# MicroController.net
KiCad netlist of a schematic drawn in Altium Designer
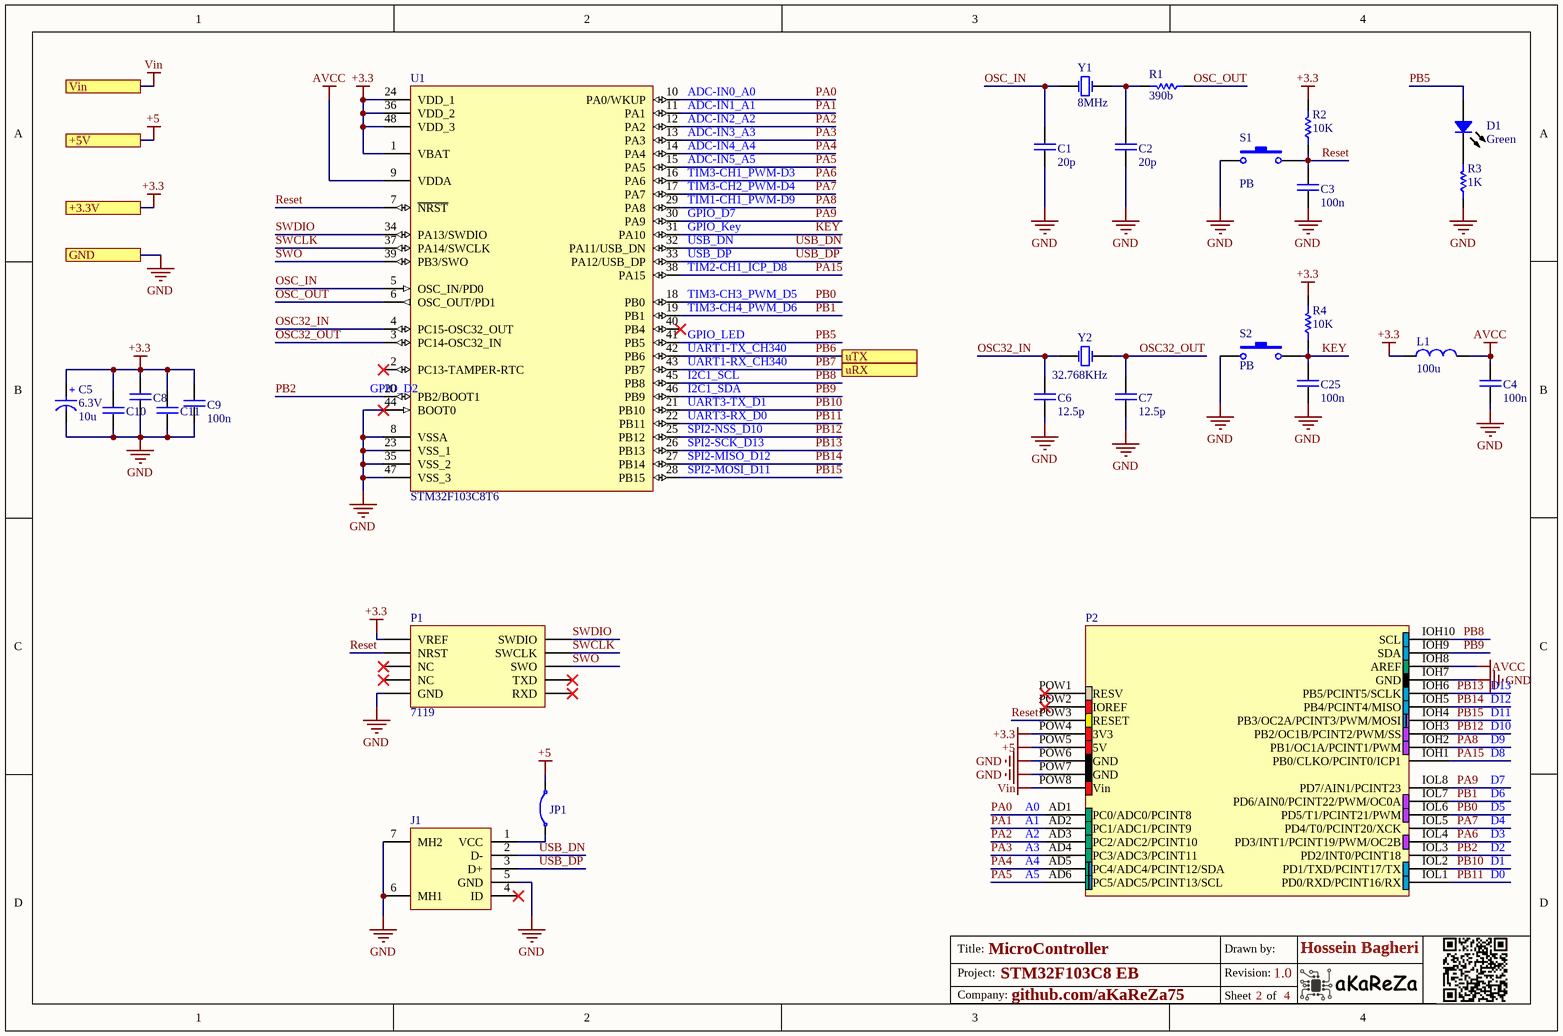
[diagram p0: MicroController.SchDoc]

(export (version "E")
  (design (tool "Eeschema 10.0.6"))
  (components
    (comp (ref "C1")
      (value "20p")
      (footprint "CAP 0603/1608")
      (description "Bipolar ceramic capacitor SMD")
      (fields (field (name "VALIDATION") "Valid"))
      (libsource (lib "aKaReZa") (part "Cap_Multi_SMD"))
    )
    (comp (ref "C2")
      (value "20p")
      (footprint "CAP 0603/1608")
      (description "Bipolar ceramic capacitor SMD")
      (fields (field (name "VALIDATION") "Valid"))
      (libsource (lib "aKaReZa") (part "Cap_Multi_SMD"))
    )
    (comp (ref "C3")
      (value "100n")
      (footprint "CAP 0805/2012")
      (description "Bipolar ceramic capacitor SMD")
      (fields (field (name "VALIDATION") "Valid"))
      (libsource (lib "aKaReZa") (part "Cap_Multi_SMD_100nF_0805"))
    )
    (comp (ref "C4")
      (value "100n")
      (footprint "CAP 0805/2012")
      (description "Bipolar ceramic capacitor SMD")
      (fields (field (name "VALIDATION") "Valid"))
      (libsource (lib "aKaReZa") (part "Cap_Multi_SMD_100nF_0805"))
    )
    (comp (ref "C5")
      (value "10u")
      (footprint "SMT_C_Tantalum_A")
      (description "Tantalum Capacitor,TAJ Series-SMD")
      (fields (field (name "RATING") "6.3V") (field (name "VALIDATION") "Valid"))
      (libsource (lib "aKaReZa") (part "Cap_Tantalum"))
    )
    (comp (ref "C6")
      (value "12.5p")
      (footprint "CAP 0603/1608")
      (description "Bipolar ceramic capacitor SMD")
      (fields (field (name "VALIDATION") "Valid"))
      (libsource (lib "aKaReZa") (part "Cap_Multi_SMD"))
    )
    (comp (ref "C7")
      (value "12.5p")
      (footprint "CAP 0603/1608")
      (description "Bipolar ceramic capacitor SMD")
      (fields (field (name "VALIDATION") "Valid"))
      (libsource (lib "aKaReZa") (part "Cap_Multi_SMD"))
    )
    (comp (ref "C8")
      (value "100n")
      (footprint "CAP 0805/2012")
      (description "Bipolar ceramic capacitor SMD")
      (fields (field (name "VALIDATION") "Valid"))
      (libsource (lib "aKaReZa") (part "Cap_Multi_SMD_100nF_0805"))
    )
    (comp (ref "C9")
      (value "100n")
      (footprint "CAP 0805/2012")
      (description "Bipolar ceramic capacitor SMD")
      (fields (field (name "VALIDATION") "Valid"))
      (libsource (lib "aKaReZa") (part "Cap_Multi_SMD_100nF_0805"))
    )
    (comp (ref "C10")
      (value "100n")
      (footprint "CAP 0805/2012")
      (description "Bipolar ceramic capacitor SMD")
      (fields (field (name "VALIDATION") "Valid"))
      (libsource (lib "aKaReZa") (part "Cap_Multi_SMD_100nF_0805"))
    )
    (comp (ref "C11")
      (value "100n")
      (footprint "CAP 0805/2012")
      (description "Bipolar ceramic capacitor SMD")
      (fields (field (name "VALIDATION") "Valid"))
      (libsource (lib "aKaReZa") (part "Cap_Multi_SMD_100nF_0805"))
    )
    (comp (ref "C25")
      (value "100n")
      (footprint "CAP 0805/2012")
      (description "Bipolar ceramic capacitor SMD")
      (fields (field (name "VALIDATION") "Valid"))
      (libsource (lib "aKaReZa") (part "Cap_Multi_SMD_100nF_0805"))
    )
    (comp (ref "D1")
      (value "Green")
      (footprint "LED 0805/2012 GREEN")
      (description "LED")
      (fields (field (name "VALIDATION") "Valid"))
      (libsource (lib "aKaReZa") (part "Semi_LED_SMD"))
    )
    (comp (ref "J1")
      (value "Micro")
      (footprint "USB_Micro_Standard")
      (description "USB micro female")
      (fields (field (name "VALIDATION") "NT"))
      (libsource (lib "aKaReZa") (part "Con_USB2_Micro"))
    )
    (comp (ref "JP1")
      (value "Jumper")
      (footprint "RESC2012M (0805)")
      (description "Jumper Component")
      (fields (field (name "VALIDATION") "Valid"))
      (libsource (lib "aKaReZa") (part "Other_Elec_Jumper_0805"))
    )
    (comp (ref "L1")
      (value "100u")
      (footprint "IND0805")
      (description "Inductor")
      (fields (field (name "VALIDATION") "Valid"))
      (libsource (lib "aKaReZa") (part "Ind_SMD_0805"))
    )
    (comp (ref "P1")
      (value "STLinkV3-minie")
      (footprint "IDC2.54-10PIN")
      (description "STLINK-V3MINIE debugger/programmer IDC probe for STM32 microcontrollers")
      (fields (field (name "INFLOW") "7119") (field (name "VALIDATION") "NT"))
      (libsource (lib "aKaReZa") (part "Con_Prog_STLinkV3_SWD"))
    )
    (comp (ref "P2")
      (value "UNO")
      (footprint "ARDUINO_UNO_CONNECTOR")
      (description "Arduino UNO Connector")
      (fields (field (name "VALIDATION") "NT"))
      (libsource (lib "aKaReZa") (part "Con_Arduino_UNO_Con"))
    )
    (comp (ref "R1")
      (value "390b")
      (footprint "RES 0805 (2012X06L)")
      (description "Resistor")
      (fields (field (name "VALIDATION") "Valid"))
      (libsource (lib "aKaReZa") (part "Res_SMD_0805"))
    )
    (comp (ref "R2")
      (value "10K")
      (footprint "RES 0805 (2012X06L)")
      (description "Resistor")
      (fields (field (name "VALIDATION") "Valid"))
      (libsource (lib "aKaReZa") (part "Res_SMD_0805"))
    )
    (comp (ref "R3")
      (value "1K")
      (footprint "RES 0805 (2012X06L)")
      (description "Resistor")
      (fields (field (name "VALIDATION") "Valid"))
      (libsource (lib "aKaReZa") (part "Res_SMD_0805"))
    )
    (comp (ref "R4")
      (value "10K")
      (footprint "RES 0805 (2012X06L)")
      (description "Resistor")
      (fields (field (name "VALIDATION") "Valid"))
      (libsource (lib "aKaReZa") (part "Res_SMD_0805"))
    )
    (comp (ref "S1")
      (value "PB")
      (footprint "SW_PB_SMD_2PIN_SPST_6X3X2")
      (description "SMT Tactile ‎Switch")
      (fields (field (name "VALIDATION") "Valid"))
      (libsource (lib "aKaReZa") (part "SW_PushButton_2_SMD"))
    )
    (comp (ref "S2")
      (value "PB")
      (footprint "SW_PB_SMD_2PIN_SPST_6X3X2")
      (description "SMT Tactile ‎Switch")
      (fields (field (name "VALIDATION") "Valid"))
      (libsource (lib "aKaReZa") (part "SW_PushButton_2_SMD"))
    )
    (comp (ref "U1")
      (value "STM32F103C8T6")
      (footprint "LQFP48_N")
      (description "32-Bit mircrocontroller")
      (fields (field (name "VALIDATION") "NT"))
      (libsource (lib "aKaReZa") (part "IC_MCU_STM32F103C8T6"))
    )
    (comp (ref "Y1")
      (value "8MHz")
      (footprint "XTL_2_5032")
      (description "Crystal Oscillator")
      (fields (field (name "VALIDATION") "NT"))
      (libsource (lib "aKaReZa") (part "Other_Elec_Xtal_8MHZ_SMD"))
    )
    (comp (ref "Y2")
      (value "32.768KHz")
      (footprint "XTL_2_3215")
      (description "Crystal Oscillator")
      (fields (field (name "VALIDATION") "NT"))
      (libsource (lib "aKaReZa") (part "Other_Elec_Xtal_32.768K_SMD"))
    )
  )
  (nets
    (net (code "1") (name "+3.3") (class "Default")
      (node (ref "C10") (pin "1") (pinfunction "1_1") (pintype "passive"))
      (node (ref "C11") (pin "1") (pinfunction "1_1") (pintype "passive"))
      (node (ref "C5") (pin "1") (pinfunction "+_1") (pintype "passive"))
      (node (ref "C8") (pin "1") (pinfunction "1_1") (pintype "passive"))
      (node (ref "C9") (pin "1") (pinfunction "1_1") (pintype "passive"))
      (node (ref "L1") (pin "1") (pinfunction "1_1") (pintype "passive"))
      (node (ref "P1") (pin "10") (pinfunction "VREF_10") (pintype "passive"))
      (node (ref "P2") (pin "POW4") (pinfunction "3V3_POW4") (pintype "passive"))
      (node (ref "R2") (pin "2") (pinfunction "2_2") (pintype "passive"))
      (node (ref "R4") (pin "2") (pinfunction "2_2") (pintype "passive"))
      (node (ref "U1") (pin "1") (pinfunction "VBAT_1") (pintype "power_in"))
      (node (ref "U1") (pin "24") (pinfunction "VDD_1_24") (pintype "power_in"))
      (node (ref "U1") (pin "36") (pinfunction "VDD_2_36") (pintype "power_in"))
      (node (ref "U1") (pin "48") (pinfunction "VDD_3_48") (pintype "power_in"))
    )
    (net (code "2") (name "+5") (class "Default")
      (node (ref "JP1") (pin "2") (pinfunction "2_2") (pintype "passive"))
      (node (ref "P2") (pin "POW5") (pinfunction "5V_POW5") (pintype "passive"))
    )
    (net (code "3") (name "/KEY") (class "Default")
      (node (ref "C25") (pin "1") (pinfunction "1_1") (pintype "passive"))
      (node (ref "R4") (pin "1") (pinfunction "1_1") (pintype "passive"))
      (node (ref "S2") (pin "1") (pinfunction "1_1") (pintype "passive"))
      (node (ref "U1") (pin "31") (pinfunction "PA10_31") (pintype "bidirectional"))
    )
    (net (code "4") (name "/OSC32_IN") (class "Default")
      (node (ref "C6") (pin "1") (pinfunction "1_1") (pintype "passive"))
      (node (ref "U1") (pin "4") (pinfunction "PC15-OSC32_OUT_4") (pintype "bidirectional"))
      (node (ref "Y2") (pin "1") (pinfunction "OSC1_1") (pintype "passive"))
    )
    (net (code "5") (name "/OSC32_OUT") (class "Default")
      (node (ref "C7") (pin "1") (pinfunction "1_1") (pintype "passive"))
      (node (ref "U1") (pin "3") (pinfunction "PC14-OSC32_IN_3") (pintype "bidirectional"))
      (node (ref "Y2") (pin "2") (pinfunction "OSC2_2") (pintype "passive"))
    )
    (net (code "6") (name "/OSC_IN") (class "Default")
      (node (ref "C1") (pin "1") (pinfunction "1_1") (pintype "passive"))
      (node (ref "U1") (pin "5") (pinfunction "OSC_IN/PD0_5") (pintype "input"))
      (node (ref "Y1") (pin "1") (pinfunction "OSC1_1") (pintype "passive"))
    )
    (net (code "7") (name "/OSC_OUT") (class "Default")
      (node (ref "R1") (pin "1") (pinfunction "1_1") (pintype "passive"))
      (node (ref "U1") (pin "6") (pinfunction "OSC_OUT/PD1_6") (pintype "output"))
    )
    (net (code "8") (name "/PA0") (class "Default")
      (node (ref "P2") (pin "AD1") (pinfunction "PC0/ADC0/PCINT8_AD1") (pintype "passive"))
      (node (ref "U1") (pin "10") (pinfunction "PA0/WKUP_10") (pintype "bidirectional"))
    )
    (net (code "9") (name "/PA1") (class "Default")
      (node (ref "P2") (pin "AD2") (pinfunction "PC1/ADC1/PCINT9_AD2") (pintype "passive"))
      (node (ref "U1") (pin "11") (pinfunction "PA1_11") (pintype "bidirectional"))
    )
    (net (code "10") (name "/PA2") (class "Default")
      (node (ref "P2") (pin "AD3") (pinfunction "PC2/ADC2/PCINT10_AD3") (pintype "passive"))
      (node (ref "U1") (pin "12") (pinfunction "PA2_12") (pintype "bidirectional"))
    )
    (net (code "11") (name "/PA3") (class "Default")
      (node (ref "P2") (pin "AD4") (pinfunction "PC3/ADC3/PCINT11_AD4") (pintype "passive"))
      (node (ref "U1") (pin "13") (pinfunction "PA3_13") (pintype "bidirectional"))
    )
    (net (code "12") (name "/PA4") (class "Default")
      (node (ref "P2") (pin "AD5") (pinfunction "PC4/ADC4/PCINT12/SDA_AD5") (pintype "passive"))
      (node (ref "U1") (pin "14") (pinfunction "PA4_14") (pintype "bidirectional"))
    )
    (net (code "13") (name "/PA5") (class "Default")
      (node (ref "P2") (pin "AD6") (pinfunction "PC5/ADC5/PCINT13/SCL_AD6") (pintype "passive"))
      (node (ref "U1") (pin "15") (pinfunction "PA5_15") (pintype "bidirectional"))
    )
    (net (code "14") (name "/PA6") (class "Default")
      (node (ref "P2") (pin "IOL4") (pinfunction "PD3/INT1/PCINT19/PWM/OC2B_IOL4") (pintype "passive"))
      (node (ref "U1") (pin "16") (pinfunction "PA6_16") (pintype "bidirectional"))
    )
    (net (code "15") (name "/PA7") (class "Default")
      (node (ref "P2") (pin "IOL5") (pinfunction "PD4/T0/PCINT20/XCK_IOL5") (pintype "passive"))
      (node (ref "U1") (pin "17") (pinfunction "PA7_17") (pintype "bidirectional"))
    )
    (net (code "16") (name "/PA8") (class "Default")
      (node (ref "P2") (pin "IOH2") (pinfunction "PB1/OC1A/PCINT1/PWM_IOH2") (pintype "passive"))
      (node (ref "U1") (pin "29") (pinfunction "PA8_29") (pintype "bidirectional"))
    )
    (net (code "17") (name "/PA9") (class "Default")
      (node (ref "P2") (pin "IOL8") (pinfunction "PD7/AIN1/PCINT23_IOL8") (pintype "passive"))
      (node (ref "U1") (pin "30") (pinfunction "PA9_30") (pintype "bidirectional"))
    )
    (net (code "18") (name "/PA15") (class "Default")
      (node (ref "P2") (pin "IOH1") (pinfunction "PB0/CLKO/PCINT0/ICP1_IOH1") (pintype "passive"))
      (node (ref "U1") (pin "38") (pinfunction "PA15_38") (pintype "bidirectional"))
    )
    (net (code "19") (name "/PB0") (class "Default")
      (node (ref "P2") (pin "IOL6") (pinfunction "PD5/T1/PCINT21/PWM_IOL6") (pintype "passive"))
      (node (ref "U1") (pin "18") (pinfunction "PB0_18") (pintype "bidirectional"))
    )
    (net (code "20") (name "/PB1") (class "Default")
      (node (ref "P2") (pin "IOL7") (pinfunction "PD6/AIN0/PCINT22/PWM/OC0A_IOL7") (pintype "passive"))
      (node (ref "U1") (pin "19") (pinfunction "PB1_19") (pintype "bidirectional"))
    )
    (net (code "21") (name "/PB2") (class "Default")
      (node (ref "P2") (pin "IOL3") (pinfunction "PD2/INT0/PCINT18_IOL3") (pintype "passive"))
      (node (ref "U1") (pin "20") (pinfunction "PB2/BOOT1_20") (pintype "bidirectional"))
    )
    (net (code "22") (name "/PB5") (class "Default")
      (node (ref "D1") (pin "1") (pinfunction "1_1") (pintype "passive"))
      (node (ref "U1") (pin "41") (pinfunction "PB5_41") (pintype "bidirectional"))
    )
    (net (code "23") (name "/PB6") (class "Default")
      (node (ref "U1") (pin "42") (pinfunction "PB6_42") (pintype "bidirectional"))
    )
    (net (code "24") (name "/PB7") (class "Default")
      (node (ref "U1") (pin "43") (pinfunction "PB7_43") (pintype "bidirectional"))
    )
    (net (code "25") (name "/PB8") (class "Default")
      (node (ref "P2") (pin "IOH10") (pinfunction "SCL_IOH10") (pintype "passive"))
      (node (ref "U1") (pin "45") (pinfunction "PB8_45") (pintype "bidirectional"))
    )
    (net (code "26") (name "/PB9") (class "Default")
      (node (ref "P2") (pin "IOH9") (pinfunction "SDA_IOH9") (pintype "passive"))
      (node (ref "U1") (pin "46") (pinfunction "PB9_46") (pintype "bidirectional"))
    )
    (net (code "27") (name "/PB10") (class "Default")
      (node (ref "P2") (pin "IOL2") (pinfunction "PD1/TXD/PCINT17/TX_IOL2") (pintype "passive"))
      (node (ref "U1") (pin "21") (pinfunction "PB10_21") (pintype "bidirectional"))
    )
    (net (code "28") (name "/PB11") (class "Default")
      (node (ref "P2") (pin "IOL1") (pinfunction "PD0/RXD/PCINT16/RX_IOL1") (pintype "passive"))
      (node (ref "U1") (pin "22") (pinfunction "PB11_22") (pintype "bidirectional"))
    )
    (net (code "29") (name "/PB12") (class "Default")
      (node (ref "P2") (pin "IOH3") (pinfunction "PB2/OC1B/PCINT2/PWM/SS_IOH3") (pintype "passive"))
      (node (ref "U1") (pin "25") (pinfunction "PB12_25") (pintype "bidirectional"))
    )
    (net (code "30") (name "/PB13") (class "Default")
      (node (ref "P2") (pin "IOH6") (pinfunction "PB5/PCINT5/SCLK_IOH6") (pintype "passive"))
      (node (ref "U1") (pin "26") (pinfunction "PB13_26") (pintype "bidirectional"))
    )
    (net (code "31") (name "/PB14") (class "Default")
      (node (ref "P2") (pin "IOH5") (pinfunction "PB4/PCINT4/MISO_IOH5") (pintype "passive"))
      (node (ref "U1") (pin "27") (pinfunction "PB14_27") (pintype "bidirectional"))
    )
    (net (code "32") (name "/PB15") (class "Default")
      (node (ref "P2") (pin "IOH4") (pinfunction "PB3/OC2A/PCINT3/PWM/MOSI_IOH4") (pintype "passive"))
      (node (ref "U1") (pin "28") (pinfunction "PB15_28") (pintype "bidirectional"))
    )
    (net (code "33") (name "/Reset") (class "Default")
      (node (ref "C3") (pin "1") (pinfunction "1_1") (pintype "passive"))
      (node (ref "P1") (pin "8") (pinfunction "NRST_8") (pintype "passive"))
      (node (ref "P2") (pin "POW3") (pinfunction "RESET_POW3") (pintype "passive"))
      (node (ref "R2") (pin "1") (pinfunction "1_1") (pintype "passive"))
      (node (ref "S1") (pin "2") (pinfunction "2_2") (pintype "passive"))
      (node (ref "U1") (pin "7") (pinfunction "~{NRST}_7") (pintype "bidirectional"))
    )
    (net (code "34") (name "/SWCLK") (class "Default")
      (node (ref "P1") (pin "7") (pinfunction "SWCLK_7") (pintype "passive"))
      (node (ref "U1") (pin "37") (pinfunction "PA14/SWCLK_37") (pintype "bidirectional"))
    )
    (net (code "35") (name "/SWDIO") (class "Default")
      (node (ref "P1") (pin "5") (pinfunction "SWDIO_5") (pintype "passive"))
      (node (ref "U1") (pin "34") (pinfunction "PA13/SWDIO_34") (pintype "bidirectional"))
    )
    (net (code "36") (name "/SWO") (class "Default")
      (node (ref "P1") (pin "9") (pinfunction "SWO_9") (pintype "passive"))
      (node (ref "U1") (pin "39") (pinfunction "PB3/SWO_39") (pintype "bidirectional"))
    )
    (net (code "37") (name "/USB_DN") (class "Default")
      (node (ref "J1") (pin "2") (pinfunction "D-_2") (pintype "passive"))
      (node (ref "U1") (pin "32") (pinfunction "PA11/USB_DN_32") (pintype "bidirectional"))
    )
    (net (code "38") (name "/USB_DP") (class "Default")
      (node (ref "J1") (pin "3") (pinfunction "D+_3") (pintype "passive"))
      (node (ref "U1") (pin "33") (pinfunction "PA12/USB_DP_33") (pintype "bidirectional"))
    )
    (net (code "39") (name "AVCC") (class "Default")
      (node (ref "C4") (pin "1") (pinfunction "1_1") (pintype "passive"))
      (node (ref "L1") (pin "2") (pinfunction "2_2") (pintype "passive"))
      (node (ref "P2") (pin "IOH8") (pinfunction "AREF_IOH8") (pintype "passive"))
      (node (ref "U1") (pin "9") (pinfunction "VDDA_9") (pintype "power_in"))
    )
    (net (code "40") (name "GND") (class "Default")
      (node (ref "C1") (pin "2") (pinfunction "2_2") (pintype "passive"))
      (node (ref "C10") (pin "2") (pinfunction "2_2") (pintype "passive"))
      (node (ref "C11") (pin "2") (pinfunction "2_2") (pintype "passive"))
      (node (ref "C2") (pin "2") (pinfunction "2_2") (pintype "passive"))
      (node (ref "C25") (pin "2") (pinfunction "2_2") (pintype "passive"))
      (node (ref "C3") (pin "2") (pinfunction "2_2") (pintype "passive"))
      (node (ref "C4") (pin "2") (pinfunction "2_2") (pintype "passive"))
      (node (ref "C5") (pin "2") (pinfunction "-_2") (pintype "passive"))
      (node (ref "C6") (pin "2") (pinfunction "2_2") (pintype "passive"))
      (node (ref "C7") (pin "2") (pinfunction "2_2") (pintype "passive"))
      (node (ref "C8") (pin "2") (pinfunction "2_2") (pintype "passive"))
      (node (ref "C9") (pin "2") (pinfunction "2_2") (pintype "passive"))
      (node (ref "J1") (pin "5") (pinfunction "GND_5") (pintype "passive"))
      (node (ref "J1") (pin "6") (pinfunction "MH1_6") (pintype "passive"))
      (node (ref "J1") (pin "7") (pinfunction "MH2_7") (pintype "passive"))
      (node (ref "P1") (pin "2") (pinfunction "GND_2") (pintype "passive"))
      (node (ref "P2") (pin "IOH7") (pinfunction "GND_IOH7") (pintype "passive"))
      (node (ref "P2") (pin "POW6") (pinfunction "GND_POW6") (pintype "passive"))
      (node (ref "P2") (pin "POW7") (pinfunction "GND_POW7") (pintype "passive"))
      (node (ref "R3") (pin "1") (pinfunction "1_1") (pintype "passive"))
      (node (ref "S1") (pin "1") (pinfunction "1_1") (pintype "passive"))
      (node (ref "S2") (pin "2") (pinfunction "2_2") (pintype "passive"))
      (node (ref "U1") (pin "23") (pinfunction "VSS_1_23") (pintype "power_in"))
      (node (ref "U1") (pin "35") (pinfunction "VSS_2_35") (pintype "power_in"))
      (node (ref "U1") (pin "44") (pinfunction "BOOT0_44") (pintype "input"))
      (node (ref "U1") (pin "47") (pinfunction "VSS_3_47") (pintype "power_in"))
      (node (ref "U1") (pin "8") (pinfunction "VSSA_8") (pintype "power_in"))
    )
    (net (code "41") (name "Net-(D1-Pad2)") (class "Default")
      (node (ref "D1") (pin "2") (pinfunction "2_2") (pintype "passive"))
      (node (ref "R3") (pin "2") (pinfunction "2_2") (pintype "passive"))
    )
    (net (code "42") (name "Net-(J1-VCC)") (class "Default")
      (node (ref "J1") (pin "1") (pinfunction "VCC_1") (pintype "passive"))
      (node (ref "JP1") (pin "1") (pinfunction "1_1") (pintype "passive"))
    )
    (net (code "43") (name "Net-(Y1-OSC2)") (class "Default")
      (node (ref "C2") (pin "1") (pinfunction "1_1") (pintype "passive"))
      (node (ref "R1") (pin "2") (pinfunction "2_2") (pintype "passive"))
      (node (ref "Y1") (pin "2") (pinfunction "OSC2_2") (pintype "passive"))
    )
    (net (code "44") (name "Vin") (class "Default")
      (node (ref "P2") (pin "POW8") (pinfunction "Vin_POW8") (pintype "passive"))
    )
    (net (code "45") (name "unconnected-(J1-ID-Pad4)") (class "Default")
      (node (ref "J1") (pin "4") (pinfunction "ID_4") (pintype "passive+no_connect"))
    )
    (net (code "46") (name "unconnected-(P1-NC-Pad1)") (class "Default")
      (node (ref "P1") (pin "1") (pinfunction "NC_1") (pintype "passive+no_connect"))
    )
    (net (code "47") (name "unconnected-(P1-NC-Pad3)") (class "Default")
      (node (ref "P1") (pin "3") (pinfunction "NC_3") (pintype "passive+no_connect"))
    )
    (net (code "48") (name "unconnected-(P1-RXD-Pad6)") (class "Default")
      (node (ref "P1") (pin "6") (pinfunction "RXD_6") (pintype "passive+no_connect"))
    )
    (net (code "49") (name "unconnected-(P1-TXD-Pad4)") (class "Default")
      (node (ref "P1") (pin "4") (pinfunction "TXD_4") (pintype "passive+no_connect"))
    )
    (net (code "50") (name "unconnected-(P2-IOREF-PadPOW2)") (class "Default")
      (node (ref "P2") (pin "POW2") (pinfunction "IOREF_POW2") (pintype "passive+no_connect"))
    )
    (net (code "51") (name "unconnected-(P2-RESV-PadPOW1)") (class "Default")
      (node (ref "P2") (pin "POW1") (pinfunction "RESV_POW1") (pintype "passive+no_connect"))
    )
    (net (code "52") (name "unconnected-(U1-PB4-Pad40)") (class "Default")
      (node (ref "U1") (pin "40") (pinfunction "PB4_40") (pintype "bidirectional+no_connect"))
    )
    (net (code "53") (name "unconnected-(U1-PC13-TAMPER-RTC-Pad2)") (class "Default")
      (node (ref "U1") (pin "2") (pinfunction "PC13-TAMPER-RTC_2") (pintype "bidirectional+no_connect"))
    )
  )
)
